# Shruthi-Analog-SMR4-mkII-v02-outline-log.net
KiCad netlist of a schematic drawn in EAGLE
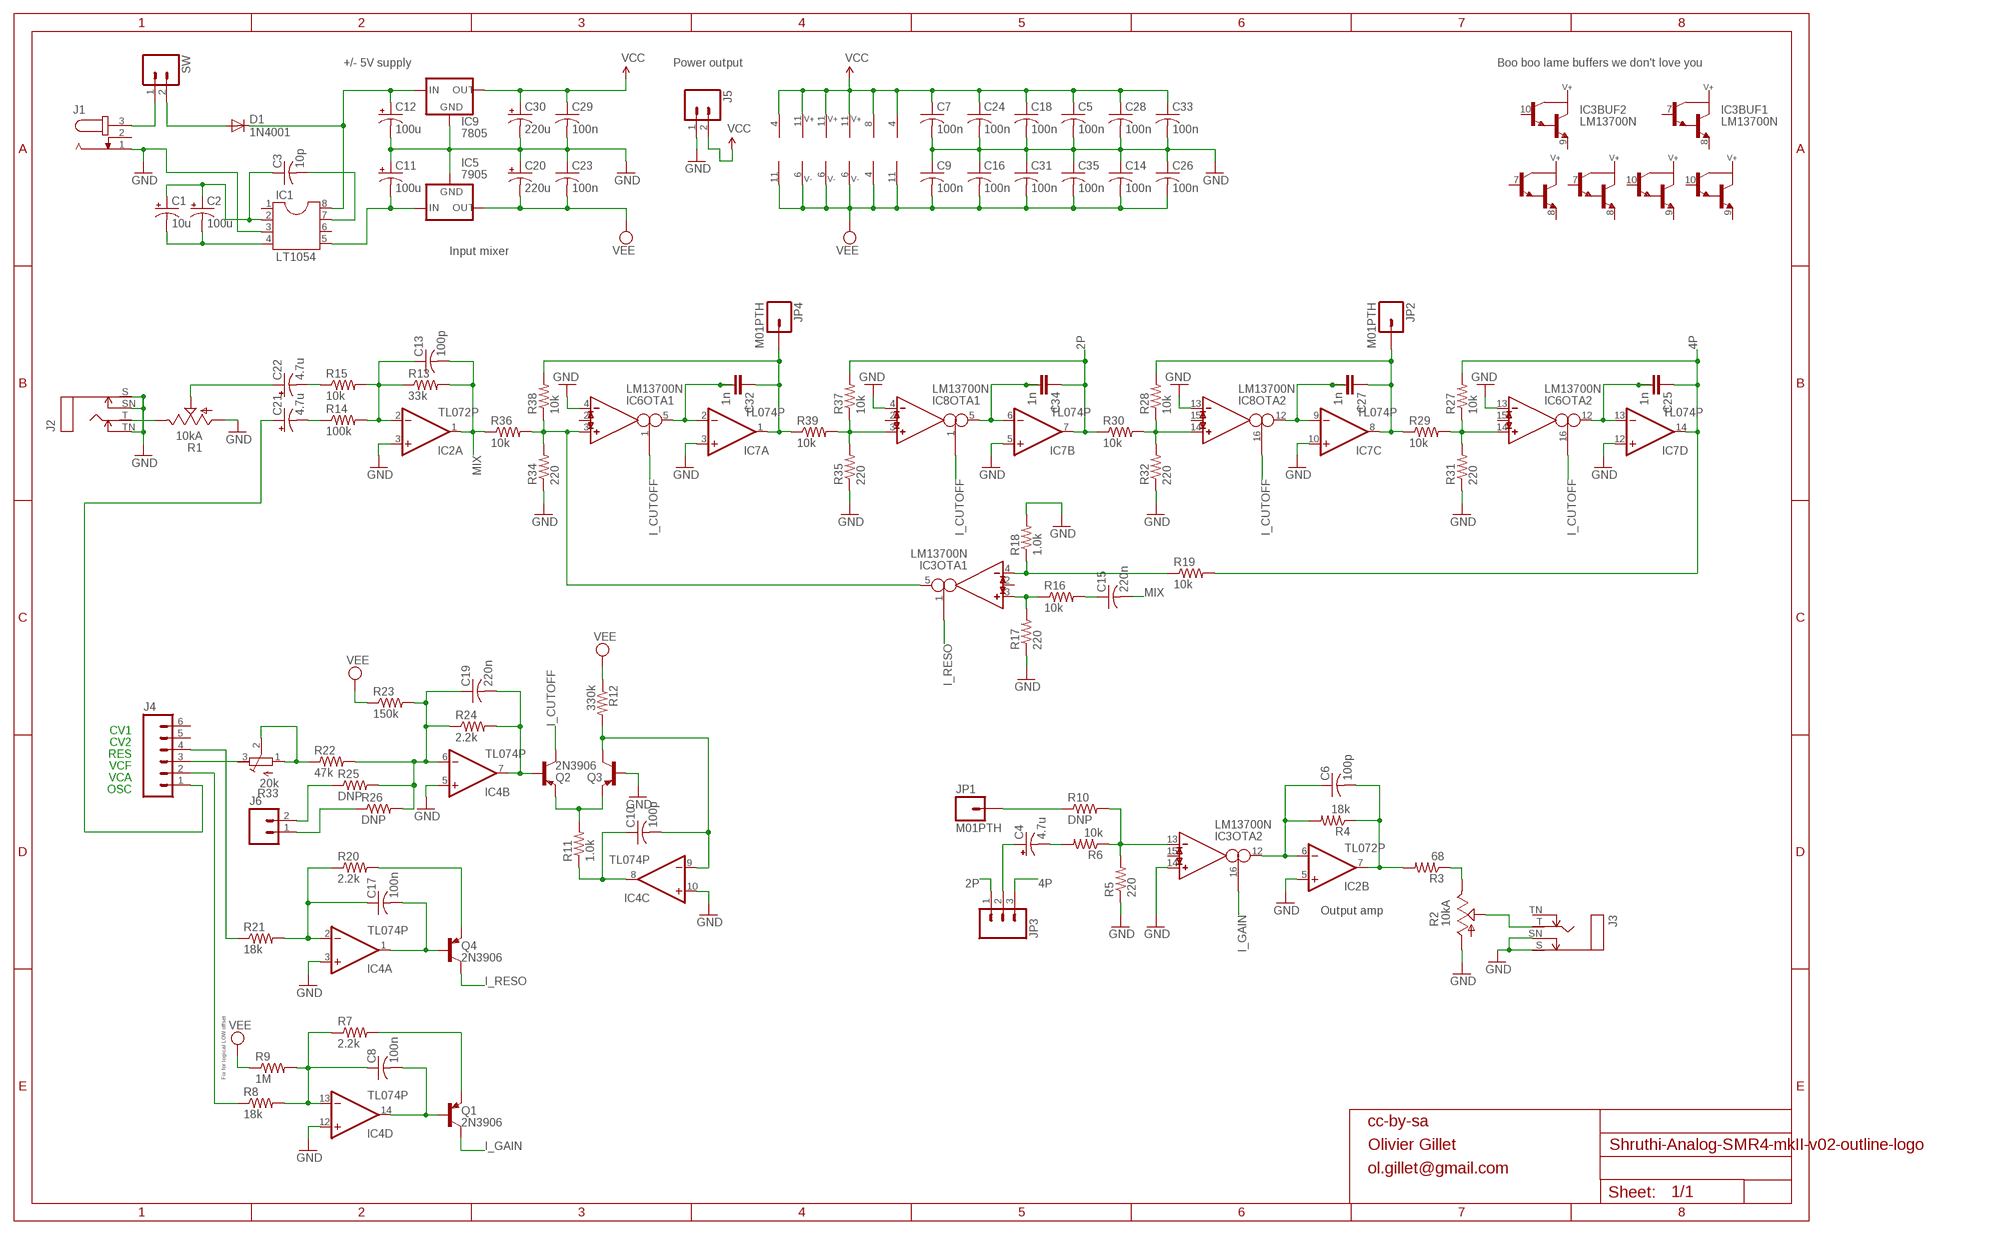
[diagram p0: schematic, sheet 1]

(export (version "E")
  (design (tool "Eeschema 10.0.6"))
  (components
    (comp (ref "C1")
      (value "10u")
      (footprint "eagle-import:E2,5-5")
      (libsource (lib "eagle-import") (part "CPOL-USE2.5-5"))
    )
    (comp (ref "C2")
      (value "100u")
      (footprint "eagle-import:E2,5-6")
      (libsource (lib "eagle-import") (part "CPOL-USE2.5-6"))
    )
    (comp (ref "C3")
      (value "10p")
      (footprint "eagle-import:C025-025X050")
      (libsource (lib "eagle-import") (part "C-US025-025X050"))
    )
    (comp (ref "C4")
      (value "4.7u")
      (footprint "eagle-import:E2,5-6")
      (libsource (lib "eagle-import") (part "CPOL-USE2.5-6"))
    )
    (comp (ref "C5")
      (value "100n")
      (footprint "eagle-import:C025-025X050")
      (libsource (lib "eagle-import") (part "C-US025-025X050"))
    )
    (comp (ref "C6")
      (value "100p")
      (footprint "eagle-import:C025-025X050")
      (libsource (lib "eagle-import") (part "C-US025-025X050"))
    )
    (comp (ref "C7")
      (value "100n")
      (footprint "eagle-import:C025-025X050")
      (libsource (lib "eagle-import") (part "C-US025-025X050"))
    )
    (comp (ref "C8")
      (value "100n")
      (footprint "eagle-import:C025-025X050")
      (libsource (lib "eagle-import") (part "C-US025-025X050"))
    )
    (comp (ref "C9")
      (value "100n")
      (footprint "eagle-import:C025-025X050")
      (libsource (lib "eagle-import") (part "C-US025-025X050"))
    )
    (comp (ref "C10")
      (value "100p")
      (footprint "eagle-import:C025-025X050")
      (libsource (lib "eagle-import") (part "C-US025-025X050"))
    )
    (comp (ref "C11")
      (value "100u")
      (footprint "eagle-import:E2,5-7")
      (libsource (lib "eagle-import") (part "CPOL-USE2.5-7"))
    )
    (comp (ref "C12")
      (value "100u")
      (footprint "eagle-import:E2,5-7")
      (libsource (lib "eagle-import") (part "CPOL-USE2.5-7"))
    )
    (comp (ref "C13")
      (value "100p")
      (footprint "eagle-import:C025-025X050")
      (libsource (lib "eagle-import") (part "C-US025-025X050"))
    )
    (comp (ref "C14")
      (value "100n")
      (footprint "eagle-import:C025-025X050")
      (libsource (lib "eagle-import") (part "C-US025-025X050"))
    )
    (comp (ref "C15")
      (value "220n")
      (footprint "eagle-import:C025-025X050")
      (libsource (lib "eagle-import") (part "C-US025-025X050"))
    )
    (comp (ref "C16")
      (value "100n")
      (footprint "eagle-import:C025-025X050")
      (libsource (lib "eagle-import") (part "C-US025-025X050"))
    )
    (comp (ref "C17")
      (value "100n")
      (footprint "eagle-import:C025-025X050")
      (libsource (lib "eagle-import") (part "C-US025-025X050"))
    )
    (comp (ref "C18")
      (value "100n")
      (footprint "eagle-import:C025-025X050")
      (libsource (lib "eagle-import") (part "C-US025-025X050"))
    )
    (comp (ref "C19")
      (value "220n")
      (footprint "eagle-import:C025-025X050")
      (libsource (lib "eagle-import") (part "C-US025-025X050"))
    )
    (comp (ref "C20")
      (value "220u")
      (footprint "eagle-import:E5-10,5")
      (libsource (lib "eagle-import") (part "CPOL-USE5-10.5"))
    )
    (comp (ref "C21")
      (value "4.7u")
      (footprint "eagle-import:E2,5-6")
      (libsource (lib "eagle-import") (part "CPOL-USE2.5-6"))
    )
    (comp (ref "C22")
      (value "4.7u")
      (footprint "eagle-import:E2,5-6")
      (libsource (lib "eagle-import") (part "CPOL-USE2.5-6"))
    )
    (comp (ref "C23")
      (value "100n")
      (footprint "eagle-import:C025-025X050")
      (libsource (lib "eagle-import") (part "C-US025-025X050"))
    )
    (comp (ref "C24")
      (value "100n")
      (footprint "eagle-import:C025-025X050")
      (libsource (lib "eagle-import") (part "C-US025-025X050"))
    )
    (comp (ref "C25")
      (value "1n")
      (footprint "eagle-import:C2.5_5-2")
      (libsource (lib "eagle-import") (part "C-2.5-5/2"))
    )
    (comp (ref "C26")
      (value "100n")
      (footprint "eagle-import:C025-025X050")
      (libsource (lib "eagle-import") (part "C-US025-025X050"))
    )
    (comp (ref "C27")
      (value "1n")
      (footprint "eagle-import:C2.5_5-2")
      (libsource (lib "eagle-import") (part "C-2.5-5/2"))
    )
    (comp (ref "C28")
      (value "100n")
      (footprint "eagle-import:C025-025X050")
      (libsource (lib "eagle-import") (part "C-US025-025X050"))
    )
    (comp (ref "C29")
      (value "100n")
      (footprint "eagle-import:C025-025X050")
      (libsource (lib "eagle-import") (part "C-US025-025X050"))
    )
    (comp (ref "C30")
      (value "220u")
      (footprint "eagle-import:E5-10,5")
      (libsource (lib "eagle-import") (part "CPOL-USE5-10.5"))
    )
    (comp (ref "C31")
      (value "100n")
      (footprint "eagle-import:C025-025X050")
      (libsource (lib "eagle-import") (part "C-US025-025X050"))
    )
    (comp (ref "C32")
      (value "1n")
      (footprint "eagle-import:C2.5_5-2")
      (libsource (lib "eagle-import") (part "C-2.5-5/2"))
    )
    (comp (ref "C33")
      (value "100n")
      (footprint "eagle-import:C025-025X050")
      (libsource (lib "eagle-import") (part "C-US025-025X050"))
    )
    (comp (ref "C34")
      (value "1n")
      (footprint "eagle-import:C2.5_5-2")
      (libsource (lib "eagle-import") (part "C-2.5-5/2"))
    )
    (comp (ref "C35")
      (value "100n")
      (footprint "eagle-import:C025-025X050")
      (libsource (lib "eagle-import") (part "C-US025-025X050"))
    )
    (comp (ref "D1")
      (value "1N4001")
      (footprint "eagle-import:DO41-10")
      (libsource (lib "eagle-import") (part "1N4004"))
    )
    (comp (ref "IC1")
      (value "LT1054")
      (footprint "eagle-import:DIL08")
      (libsource (lib "eagle-import") (part "DIL8"))
    )
    (comp (ref "IC2")
      (value "TL072P")
      (footprint "eagle-import:DIL08")
      (libsource (lib "eagle-import") (part "TL072P"))
    )
    (comp (ref "IC3")
      (value "LM13700N")
      (footprint "eagle-import:DIL16")
      (libsource (lib "eagle-import") (part "LM13700N"))
    )
    (comp (ref "IC4")
      (value "TL074P")
      (footprint "eagle-import:DIL14")
      (libsource (lib "eagle-import") (part "TL084P"))
    )
    (comp (ref "IC5")
      (value "7905")
      (footprint "eagle-import:79XXS")
      (libsource (lib "eagle-import") (part "79XXS"))
    )
    (comp (ref "IC6")
      (value "LM13700N")
      (footprint "eagle-import:DIL16")
      (libsource (lib "eagle-import") (part "LM13700N"))
    )
    (comp (ref "IC7")
      (value "TL074P")
      (footprint "eagle-import:DIL14")
      (libsource (lib "eagle-import") (part "TL084P"))
    )
    (comp (ref "IC8")
      (value "LM13700N")
      (footprint "eagle-import:DIL16")
      (libsource (lib "eagle-import") (part "LM13700N"))
    )
    (comp (ref "IC9")
      (value "7805")
      (footprint "eagle-import:78XXS")
      (libsource (lib "eagle-import") (part "78XXS"))
    )
    (comp (ref "J1")
      (value "JACK-PLUG2")
      (footprint "eagle-import:SPC4078_BIG_HOLES")
      (libsource (lib "eagle-import") (part "JACK-PLUG2"))
    )
    (comp (ref "J2")
      (value "MONOSWS")
      (footprint "eagle-import:NMJ4HC-S")
      (libsource (lib "eagle-import") (part "MONOSWS"))
    )
    (comp (ref "J3")
      (value "MONOSWS")
      (footprint "eagle-import:NMJ4HC-S")
      (libsource (lib "eagle-import") (part "MONOSWS"))
    )
    (comp (ref "J4")
      (value "M06SIP")
      (footprint "eagle-import:1X06")
      (libsource (lib "eagle-import") (part "M06SIP"))
    )
    (comp (ref "J5")
      (value "M02PTH")
      (footprint "eagle-import:1X02")
      (libsource (lib "eagle-import") (part "M02PTH"))
    )
    (comp (ref "J6")
      (value "M02PTH")
      (footprint "eagle-import:1X02")
      (libsource (lib "eagle-import") (part "M02PTH"))
    )
    (comp (ref "JP1")
      (value "M01PTH")
      (footprint "eagle-import:1X01")
      (libsource (lib "eagle-import") (part "M01PTH"))
    )
    (comp (ref "JP2")
      (value "M01PTH")
      (footprint "eagle-import:1X01")
      (libsource (lib "eagle-import") (part "M01PTH"))
    )
    (comp (ref "JP3")
      (value "M03PTH")
      (footprint "eagle-import:1X03")
      (libsource (lib "eagle-import") (part "M03PTH"))
    )
    (comp (ref "JP4")
      (value "M01PTH")
      (footprint "eagle-import:1X01")
      (libsource (lib "eagle-import") (part "M01PTH"))
    )
    (comp (ref "Q1")
      (value "2N3906")
      (footprint "eagle-import:TO92-")
      (libsource (lib "eagle-import") (part "2N3906-"))
    )
    (comp (ref "Q2")
      (value "2N3906")
      (footprint "eagle-import:TO92-")
      (libsource (lib "eagle-import") (part "2N3906-"))
    )
    (comp (ref "Q3")
      (value "2N3906")
      (footprint "eagle-import:TO92-")
      (libsource (lib "eagle-import") (part "2N3906-"))
    )
    (comp (ref "Q4")
      (value "2N3906")
      (footprint "eagle-import:TO92-")
      (libsource (lib "eagle-import") (part "2N3906-"))
    )
    (comp (ref "R1")
      (value "10kA")
      (footprint "eagle-import:CABLE_POT_6MM")
      (libsource (lib "eagle-import") (part "POT_USCABLED"))
    )
    (comp (ref "R2")
      (value "10kA")
      (footprint "eagle-import:CABLE_POT_6MM")
      (libsource (lib "eagle-import") (part "POT_USCABLED"))
    )
    (comp (ref "R3")
      (value "68")
      (footprint "eagle-import:0204_7")
      (libsource (lib "eagle-import") (part "R-US_0204/7"))
    )
    (comp (ref "R4")
      (value "18k")
      (footprint "eagle-import:0204_7")
      (libsource (lib "eagle-import") (part "R-US_0204/7"))
    )
    (comp (ref "R5")
      (value "220")
      (footprint "eagle-import:0204_7")
      (libsource (lib "eagle-import") (part "R-US_0204/7"))
    )
    (comp (ref "R6")
      (value "10k")
      (footprint "eagle-import:0204_7")
      (libsource (lib "eagle-import") (part "R-US_0204/7"))
    )
    (comp (ref "R7")
      (value "2.2k")
      (footprint "eagle-import:0204_7")
      (libsource (lib "eagle-import") (part "R-US_0204/7"))
    )
    (comp (ref "R8")
      (value "18k")
      (footprint "eagle-import:0204_7")
      (libsource (lib "eagle-import") (part "R-US_0204/7"))
    )
    (comp (ref "R9")
      (value "1M")
      (footprint "eagle-import:0204_7")
      (libsource (lib "eagle-import") (part "R-US_0204/7"))
    )
    (comp (ref "R10")
      (value "DNP")
      (footprint "eagle-import:0204V")
      (libsource (lib "eagle-import") (part "R-US_0204/2V"))
    )
    (comp (ref "R11")
      (value "1.0k")
      (footprint "eagle-import:0204_7")
      (libsource (lib "eagle-import") (part "R-US_0204/7"))
    )
    (comp (ref "R12")
      (value "330k")
      (footprint "eagle-import:0204_7")
      (libsource (lib "eagle-import") (part "R-US_0204/7"))
    )
    (comp (ref "R13")
      (value "33k")
      (footprint "eagle-import:0204_7")
      (libsource (lib "eagle-import") (part "R-US_0204/7"))
    )
    (comp (ref "R14")
      (value "100k")
      (footprint "eagle-import:0204_7")
      (libsource (lib "eagle-import") (part "R-US_0204/7"))
    )
    (comp (ref "R15")
      (value "10k")
      (footprint "eagle-import:0204_7")
      (libsource (lib "eagle-import") (part "R-US_0204/7"))
    )
    (comp (ref "R16")
      (value "10k")
      (footprint "eagle-import:0204_7")
      (libsource (lib "eagle-import") (part "R-US_0204/7"))
    )
    (comp (ref "R17")
      (value "220")
      (footprint "eagle-import:0204_7")
      (libsource (lib "eagle-import") (part "R-US_0204/7"))
    )
    (comp (ref "R18")
      (value "1.0k")
      (footprint "eagle-import:0204_7")
      (libsource (lib "eagle-import") (part "R-US_0204/7"))
    )
    (comp (ref "R19")
      (value "10k")
      (footprint "eagle-import:0204_7")
      (libsource (lib "eagle-import") (part "R-US_0204/7"))
    )
    (comp (ref "R20")
      (value "2.2k")
      (footprint "eagle-import:0204_7")
      (libsource (lib "eagle-import") (part "R-US_0204/7"))
    )
    (comp (ref "R21")
      (value "18k")
      (footprint "eagle-import:0204_7")
      (libsource (lib "eagle-import") (part "R-US_0204/7"))
    )
    (comp (ref "R22")
      (value "47k")
      (footprint "eagle-import:0204_7")
      (libsource (lib "eagle-import") (part "R-US_0204/7"))
    )
    (comp (ref "R23")
      (value "150k")
      (footprint "eagle-import:0204_7")
      (libsource (lib "eagle-import") (part "R-US_0204/7"))
    )
    (comp (ref "R24")
      (value "2.2k")
      (footprint "eagle-import:0204_7")
      (libsource (lib "eagle-import") (part "R-US_0204/7"))
    )
    (comp (ref "R25")
      (value "DNP")
      (footprint "eagle-import:0204V")
      (libsource (lib "eagle-import") (part "R-US_0204/2V"))
    )
    (comp (ref "R26")
      (value "DNP")
      (footprint "eagle-import:0204V")
      (libsource (lib "eagle-import") (part "R-US_0204/2V"))
    )
    (comp (ref "R27")
      (value "10k")
      (footprint "eagle-import:0204_7")
      (libsource (lib "eagle-import") (part "R-US_0204/7"))
    )
    (comp (ref "R28")
      (value "10k")
      (footprint "eagle-import:0204_7")
      (libsource (lib "eagle-import") (part "R-US_0204/7"))
    )
    (comp (ref "R29")
      (value "10k")
      (footprint "eagle-import:0204_7")
      (libsource (lib "eagle-import") (part "R-US_0204/7"))
    )
    (comp (ref "R30")
      (value "10k")
      (footprint "eagle-import:0204_7")
      (libsource (lib "eagle-import") (part "R-US_0204/7"))
    )
    (comp (ref "R31")
      (value "220")
      (footprint "eagle-import:0204_7")
      (libsource (lib "eagle-import") (part "R-US_0204/7"))
    )
    (comp (ref "R32")
      (value "220")
      (footprint "eagle-import:0204_7")
      (libsource (lib "eagle-import") (part "R-US_0204/7"))
    )
    (comp (ref "R33")
      (value "20k")
      (footprint "eagle-import:RTRIM3296X")
      (libsource (lib "eagle-import") (part "R-TRIMM3296X"))
    )
    (comp (ref "R34")
      (value "220")
      (footprint "eagle-import:0204_7")
      (libsource (lib "eagle-import") (part "R-US_0204/7"))
    )
    (comp (ref "R35")
      (value "220")
      (footprint "eagle-import:0204_7")
      (libsource (lib "eagle-import") (part "R-US_0204/7"))
    )
    (comp (ref "R36")
      (value "10k")
      (footprint "eagle-import:0204_7")
      (libsource (lib "eagle-import") (part "R-US_0204/7"))
    )
    (comp (ref "R37")
      (value "10k")
      (footprint "eagle-import:0204_7")
      (libsource (lib "eagle-import") (part "R-US_0204/7"))
    )
    (comp (ref "R38")
      (value "10k")
      (footprint "eagle-import:0204_7")
      (libsource (lib "eagle-import") (part "R-US_0204/7"))
    )
    (comp (ref "R39")
      (value "10k")
      (footprint "eagle-import:0204_7")
      (libsource (lib "eagle-import") (part "R-US_0204/7"))
    )
    (comp (ref "SW")
      (value "M02PTH")
      (footprint "eagle-import:1X02")
      (libsource (lib "eagle-import") (part "M02PTH"))
    )
  )
  (nets
    (net (code "1") (name "/2P") (class "Default")
      (node (ref "C34") (pin "1") (pinfunction "1_1") (pintype "passive"))
      (node (ref "IC7") (pin "7") (pinfunction "OUT_7") (pintype "output"))
      (node (ref "JP3") (pin "1") (pinfunction "1_1") (pintype "passive"))
      (node (ref "R30") (pin "1") (pinfunction "1_1") (pintype "passive"))
      (node (ref "R37") (pin "2") (pinfunction "2_2") (pintype "passive"))
    )
    (net (code "2") (name "/4P") (class "Default")
      (node (ref "C25") (pin "1") (pinfunction "1_1") (pintype "passive"))
      (node (ref "IC7") (pin "14") (pinfunction "OUT_14") (pintype "output"))
      (node (ref "JP3") (pin "3") (pinfunction "3_3") (pintype "passive"))
      (node (ref "R19") (pin "2") (pinfunction "2_2") (pintype "passive"))
      (node (ref "R27") (pin "2") (pinfunction "2_2") (pintype "passive"))
    )
    (net (code "3") (name "/I_CUTOFF") (class "Default")
      (node (ref "IC6") (pin "1") (pinfunction "I_BIAS_1") (pintype "input"))
      (node (ref "IC6") (pin "16") (pinfunction "I_BIAS_16") (pintype "input"))
      (node (ref "IC8") (pin "1") (pinfunction "I_BIAS_1") (pintype "input"))
      (node (ref "IC8") (pin "16") (pinfunction "I_BIAS_16") (pintype "input"))
      (node (ref "Q2") (pin "1") (pinfunction "C_1") (pintype "passive"))
    )
    (net (code "4") (name "/I_GAIN") (class "Default")
      (node (ref "IC3") (pin "16") (pinfunction "I_BIAS_16") (pintype "input"))
      (node (ref "Q1") (pin "1") (pinfunction "C_1") (pintype "passive"))
    )
    (net (code "5") (name "/I_RESO") (class "Default")
      (node (ref "IC3") (pin "1") (pinfunction "I_BIAS_1") (pintype "input"))
      (node (ref "Q4") (pin "1") (pinfunction "C_1") (pintype "passive"))
    )
    (net (code "6") (name "/MIX") (class "Default")
      (node (ref "C13") (pin "2") (pinfunction "2_2") (pintype "passive"))
      (node (ref "C15") (pin "2") (pinfunction "2_2") (pintype "passive"))
      (node (ref "IC2") (pin "1") (pinfunction "OUT_1") (pintype "output"))
      (node (ref "R13") (pin "2") (pinfunction "2_2") (pintype "passive"))
      (node (ref "R36") (pin "1") (pinfunction "1_1") (pintype "passive"))
    )
    (net (code "7") (name "GND") (class "Default")
      (node (ref "C11") (pin "+") (pinfunction "+_+") (pintype "passive"))
      (node (ref "C12") (pin "-") (pinfunction "-_-") (pintype "passive"))
      (node (ref "C14") (pin "1") (pinfunction "1_1") (pintype "passive"))
      (node (ref "C16") (pin "1") (pinfunction "1_1") (pintype "passive"))
      (node (ref "C18") (pin "2") (pinfunction "2_2") (pintype "passive"))
      (node (ref "C20") (pin "+") (pinfunction "+_+") (pintype "passive"))
      (node (ref "C23") (pin "1") (pinfunction "1_1") (pintype "passive"))
      (node (ref "C24") (pin "2") (pinfunction "2_2") (pintype "passive"))
      (node (ref "C26") (pin "1") (pinfunction "1_1") (pintype "passive"))
      (node (ref "C28") (pin "2") (pinfunction "2_2") (pintype "passive"))
      (node (ref "C29") (pin "2") (pinfunction "2_2") (pintype "passive"))
      (node (ref "C30") (pin "-") (pinfunction "-_-") (pintype "passive"))
      (node (ref "C31") (pin "1") (pinfunction "1_1") (pintype "passive"))
      (node (ref "C33") (pin "2") (pinfunction "2_2") (pintype "passive"))
      (node (ref "C35") (pin "1") (pinfunction "1_1") (pintype "passive"))
      (node (ref "C5") (pin "2") (pinfunction "2_2") (pintype "passive"))
      (node (ref "C7") (pin "2") (pinfunction "2_2") (pintype "passive"))
      (node (ref "C9") (pin "1") (pinfunction "1_1") (pintype "passive"))
      (node (ref "IC1") (pin "3") (pinfunction "3_3") (pintype "passive"))
      (node (ref "IC2") (pin "3") (pinfunction "+IN_3") (pintype "input"))
      (node (ref "IC2") (pin "5") (pinfunction "+IN_5") (pintype "input"))
      (node (ref "IC3") (pin "14") (pinfunction "IN_P_14") (pintype "input"))
      (node (ref "IC4") (pin "10") (pinfunction "+IN_10") (pintype "input"))
      (node (ref "IC4") (pin "12") (pinfunction "+IN_12") (pintype "input"))
      (node (ref "IC4") (pin "3") (pinfunction "+IN_3") (pintype "input"))
      (node (ref "IC4") (pin "5") (pinfunction "+IN_5") (pintype "input"))
      (node (ref "IC5") (pin "GND") (pinfunction "GND_GND") (pintype "input"))
      (node (ref "IC6") (pin "13") (pinfunction "IN_N_13") (pintype "input"))
      (node (ref "IC6") (pin "4") (pinfunction "IN_N_4") (pintype "input"))
      (node (ref "IC7") (pin "10") (pinfunction "+IN_10") (pintype "input"))
      (node (ref "IC7") (pin "12") (pinfunction "+IN_12") (pintype "input"))
      (node (ref "IC7") (pin "3") (pinfunction "+IN_3") (pintype "input"))
      (node (ref "IC7") (pin "5") (pinfunction "+IN_5") (pintype "input"))
      (node (ref "IC8") (pin "13") (pinfunction "IN_N_13") (pintype "input"))
      (node (ref "IC8") (pin "4") (pinfunction "IN_N_4") (pintype "input"))
      (node (ref "IC9") (pin "GND") (pinfunction "GND_GND") (pintype "input"))
      (node (ref "J1") (pin "1") (pinfunction "1_1") (pintype "passive"))
      (node (ref "J2") (pin "S") (pinfunction "S_S") (pintype "passive"))
      (node (ref "J2") (pin "SN") (pinfunction "SN_SN") (pintype "passive"))
      (node (ref "J2") (pin "TN") (pinfunction "TN_TN") (pintype "passive"))
      (node (ref "J3") (pin "S") (pinfunction "S_S") (pintype "passive"))
      (node (ref "J3") (pin "SN") (pinfunction "SN_SN") (pintype "passive"))
      (node (ref "J5") (pin "1") (pinfunction "1_1") (pintype "passive"))
      (node (ref "Q3") (pin "2") (pinfunction "B_2") (pintype "passive"))
      (node (ref "R1") (pin "A") (pinfunction "A_A") (pintype "passive"))
      (node (ref "R17") (pin "1") (pinfunction "1_1") (pintype "passive"))
      (node (ref "R18") (pin "2") (pinfunction "2_2") (pintype "passive"))
      (node (ref "R2") (pin "A") (pinfunction "A_A") (pintype "passive"))
      (node (ref "R31") (pin "1") (pinfunction "1_1") (pintype "passive"))
      (node (ref "R32") (pin "1") (pinfunction "1_1") (pintype "passive"))
      (node (ref "R34") (pin "1") (pinfunction "1_1") (pintype "passive"))
      (node (ref "R35") (pin "1") (pinfunction "1_1") (pintype "passive"))
      (node (ref "R5") (pin "1") (pinfunction "1_1") (pintype "passive"))
    )
    (net (code "8") (name "Net-(C1-Pad+)") (class "Default")
      (node (ref "C1") (pin "+") (pinfunction "+_+") (pintype "passive"))
      (node (ref "C2") (pin "+") (pinfunction "+_+") (pintype "passive"))
      (node (ref "C3") (pin "1") (pinfunction "1_1") (pintype "passive"))
      (node (ref "IC1") (pin "2") (pinfunction "2_2") (pintype "passive"))
    )
    (net (code "9") (name "Net-(C1-Pad-)") (class "Default")
      (node (ref "C1") (pin "-") (pinfunction "-_-") (pintype "passive"))
      (node (ref "C2") (pin "-") (pinfunction "-_-") (pintype "passive"))
      (node (ref "IC1") (pin "4") (pinfunction "4_4") (pintype "passive"))
    )
    (net (code "10") (name "Net-(C3-Pad2)") (class "Default")
      (node (ref "C3") (pin "2") (pinfunction "2_2") (pintype "passive"))
      (node (ref "IC1") (pin "7") (pinfunction "7_7") (pintype "passive"))
    )
    (net (code "11") (name "Net-(C4-Pad+)") (class "Default")
      (node (ref "C4") (pin "+") (pinfunction "+_+") (pintype "passive"))
      (node (ref "JP3") (pin "2") (pinfunction "2_2") (pintype "passive"))
    )
    (net (code "12") (name "Net-(C4-Pad-)") (class "Default")
      (node (ref "C4") (pin "-") (pinfunction "-_-") (pintype "passive"))
      (node (ref "R6") (pin "2") (pinfunction "2_2") (pintype "passive"))
    )
    (net (code "13") (name "Net-(C11-Pad-)") (class "Default")
      (node (ref "C11") (pin "-") (pinfunction "-_-") (pintype "passive"))
      (node (ref "IC1") (pin "5") (pinfunction "5_5") (pintype "passive"))
      (node (ref "IC5") (pin "IN") (pinfunction "IN_IN") (pintype "input"))
    )
    (net (code "14") (name "Net-(C12-Pad+)") (class "Default")
      (node (ref "C12") (pin "+") (pinfunction "+_+") (pintype "passive"))
      (node (ref "D1") (pin "C") (pinfunction "C_C") (pintype "passive"))
      (node (ref "IC1") (pin "8") (pinfunction "8_8") (pintype "passive"))
      (node (ref "IC9") (pin "IN") (pinfunction "IN_IN") (pintype "input"))
    )
    (net (code "15") (name "Net-(C15-Pad1)") (class "Default")
      (node (ref "C15") (pin "1") (pinfunction "1_1") (pintype "passive"))
      (node (ref "R16") (pin "2") (pinfunction "2_2") (pintype "passive"))
    )
    (net (code "16") (name "Net-(C21-Pad+)") (class "Default")
      (node (ref "C21") (pin "+") (pinfunction "+_+") (pintype "passive"))
      (node (ref "J4") (pin "1") (pinfunction "1_1") (pintype "passive"))
    )
    (net (code "17") (name "Net-(C21-Pad-)") (class "Default")
      (node (ref "C21") (pin "-") (pinfunction "-_-") (pintype "passive"))
      (node (ref "R14") (pin "1") (pinfunction "1_1") (pintype "passive"))
    )
    (net (code "18") (name "Net-(C22-Pad+)") (class "Default")
      (node (ref "C22") (pin "+") (pinfunction "+_+") (pintype "passive"))
      (node (ref "R1") (pin "S") (pinfunction "S_S") (pintype "passive"))
    )
    (net (code "19") (name "Net-(C22-Pad-)") (class "Default")
      (node (ref "C22") (pin "-") (pinfunction "-_-") (pintype "passive"))
      (node (ref "R15") (pin "1") (pinfunction "1_1") (pintype "passive"))
    )
    (net (code "20") (name "Net-(D1-PadA)") (class "Default")
      (node (ref "D1") (pin "A") (pinfunction "A_A") (pintype "passive"))
      (node (ref "SW") (pin "2") (pinfunction "2_2") (pintype "passive"))
    )
    (net (code "21") (name "Net-(IC2A--IN)") (class "Default")
      (node (ref "C13") (pin "1") (pinfunction "1_1") (pintype "passive"))
      (node (ref "IC2") (pin "2") (pinfunction "-IN_2") (pintype "input"))
      (node (ref "R13") (pin "1") (pinfunction "1_1") (pintype "passive"))
      (node (ref "R14") (pin "2") (pinfunction "2_2") (pintype "passive"))
      (node (ref "R15") (pin "2") (pinfunction "2_2") (pintype "passive"))
    )
    (net (code "22") (name "Net-(IC2B--IN)") (class "Default")
      (node (ref "C6") (pin "1") (pinfunction "1_1") (pintype "passive"))
      (node (ref "IC2") (pin "6") (pinfunction "-IN_6") (pintype "input"))
      (node (ref "IC3") (pin "12") (pinfunction "OUT_12") (pintype "output"))
      (node (ref "R4") (pin "2") (pinfunction "2_2") (pintype "passive"))
    )
    (net (code "23") (name "Net-(IC2B-OUT)") (class "Default")
      (node (ref "C6") (pin "2") (pinfunction "2_2") (pintype "passive"))
      (node (ref "IC2") (pin "7") (pinfunction "OUT_7") (pintype "output"))
      (node (ref "R3") (pin "2") (pinfunction "2_2") (pintype "passive"))
      (node (ref "R4") (pin "1") (pinfunction "1_1") (pintype "passive"))
    )
    (net (code "24") (name "Net-(IC3C-IN_N)") (class "Default")
      (node (ref "IC3") (pin "4") (pinfunction "IN_N_4") (pintype "input"))
      (node (ref "R18") (pin "1") (pinfunction "1_1") (pintype "passive"))
      (node (ref "R19") (pin "1") (pinfunction "1_1") (pintype "passive"))
    )
    (net (code "25") (name "Net-(IC3C-IN_P)") (class "Default")
      (node (ref "IC3") (pin "3") (pinfunction "IN_P_3") (pintype "input"))
      (node (ref "R16") (pin "1") (pinfunction "1_1") (pintype "passive"))
      (node (ref "R17") (pin "2") (pinfunction "2_2") (pintype "passive"))
    )
    (net (code "26") (name "Net-(IC3C-OUT)") (class "Default")
      (node (ref "IC3") (pin "5") (pinfunction "OUT_5") (pintype "output"))
      (node (ref "IC6") (pin "3") (pinfunction "IN_P_3") (pintype "input"))
      (node (ref "R34") (pin "2") (pinfunction "2_2") (pintype "passive"))
      (node (ref "R36") (pin "2") (pinfunction "2_2") (pintype "passive"))
      (node (ref "R38") (pin "1") (pinfunction "1_1") (pintype "passive"))
    )
    (net (code "27") (name "Net-(IC3D-IN_N)") (class "Default")
      (node (ref "IC3") (pin "13") (pinfunction "IN_N_13") (pintype "input"))
      (node (ref "R10") (pin "2") (pinfunction "2_2") (pintype "passive"))
      (node (ref "R5") (pin "2") (pinfunction "2_2") (pintype "passive"))
      (node (ref "R6") (pin "1") (pinfunction "1_1") (pintype "passive"))
    )
    (net (code "28") (name "Net-(IC4A--IN)") (class "Default")
      (node (ref "C17") (pin "1") (pinfunction "1_1") (pintype "passive"))
      (node (ref "IC4") (pin "2") (pinfunction "-IN_2") (pintype "input"))
      (node (ref "R20") (pin "1") (pinfunction "1_1") (pintype "passive"))
      (node (ref "R21") (pin "2") (pinfunction "2_2") (pintype "passive"))
    )
    (net (code "29") (name "Net-(IC4A-OUT)") (class "Default")
      (node (ref "C17") (pin "2") (pinfunction "2_2") (pintype "passive"))
      (node (ref "IC4") (pin "1") (pinfunction "OUT_1") (pintype "output"))
      (node (ref "Q4") (pin "2") (pinfunction "B_2") (pintype "passive"))
    )
    (net (code "30") (name "Net-(IC4B--IN)") (class "Default")
      (node (ref "C19") (pin "1") (pinfunction "1_1") (pintype "passive"))
      (node (ref "IC4") (pin "6") (pinfunction "-IN_6") (pintype "input"))
      (node (ref "R22") (pin "2") (pinfunction "2_2") (pintype "passive"))
      (node (ref "R23") (pin "2") (pinfunction "2_2") (pintype "passive"))
      (node (ref "R24") (pin "1") (pinfunction "1_1") (pintype "passive"))
      (node (ref "R25") (pin "2") (pinfunction "2_2") (pintype "passive"))
      (node (ref "R26") (pin "2") (pinfunction "2_2") (pintype "passive"))
    )
    (net (code "31") (name "Net-(IC4B-OUT)") (class "Default")
      (node (ref "C19") (pin "2") (pinfunction "2_2") (pintype "passive"))
      (node (ref "IC4") (pin "7") (pinfunction "OUT_7") (pintype "output"))
      (node (ref "Q2") (pin "2") (pinfunction "B_2") (pintype "passive"))
      (node (ref "R24") (pin "2") (pinfunction "2_2") (pintype "passive"))
    )
    (net (code "32") (name "Net-(IC4C--IN)") (class "Default")
      (node (ref "C10") (pin "2") (pinfunction "2_2") (pintype "passive"))
      (node (ref "IC4") (pin "9") (pinfunction "-IN_9") (pintype "input"))
      (node (ref "Q3") (pin "1") (pinfunction "C_1") (pintype "passive"))
      (node (ref "R12") (pin "2") (pinfunction "2_2") (pintype "passive"))
    )
    (net (code "33") (name "Net-(IC4C-OUT)") (class "Default")
      (node (ref "C10") (pin "1") (pinfunction "1_1") (pintype "passive"))
      (node (ref "IC4") (pin "8") (pinfunction "OUT_8") (pintype "output"))
      (node (ref "R11") (pin "1") (pinfunction "1_1") (pintype "passive"))
    )
    (net (code "34") (name "Net-(IC4D--IN)") (class "Default")
      (node (ref "C8") (pin "1") (pinfunction "1_1") (pintype "passive"))
      (node (ref "IC4") (pin "13") (pinfunction "-IN_13") (pintype "input"))
      (node (ref "R7") (pin "1") (pinfunction "1_1") (pintype "passive"))
      (node (ref "R8") (pin "2") (pinfunction "2_2") (pintype "passive"))
      (node (ref "R9") (pin "2") (pinfunction "2_2") (pintype "passive"))
    )
    (net (code "35") (name "Net-(IC4D-OUT)") (class "Default")
      (node (ref "C8") (pin "2") (pinfunction "2_2") (pintype "passive"))
      (node (ref "IC4") (pin "14") (pinfunction "OUT_14") (pintype "output"))
      (node (ref "Q1") (pin "2") (pinfunction "B_2") (pintype "passive"))
    )
    (net (code "36") (name "Net-(IC6C-OUT)") (class "Default")
      (node (ref "C32") (pin "2") (pinfunction "2_2") (pintype "passive"))
      (node (ref "C32") (pin "3") (pinfunction "3_3") (pintype "passive"))
      (node (ref "IC6") (pin "5") (pinfunction "OUT_5") (pintype "output"))
      (node (ref "IC7") (pin "2") (pinfunction "-IN_2") (pintype "input"))
    )
    (net (code "37") (name "Net-(IC6D-IN_P)") (class "Default")
      (node (ref "IC6") (pin "14") (pinfunction "IN_P_14") (pintype "input"))
      (node (ref "R27") (pin "1") (pinfunction "1_1") (pintype "passive"))
      (node (ref "R29") (pin "2") (pinfunction "2_2") (pintype "passive"))
      (node (ref "R31") (pin "2") (pinfunction "2_2") (pintype "passive"))
    )
    (net (code "38") (name "Net-(IC6D-OUT)") (class "Default")
      (node (ref "C25") (pin "2") (pinfunction "2_2") (pintype "passive"))
      (node (ref "C25") (pin "3") (pinfunction "3_3") (pintype "passive"))
      (node (ref "IC6") (pin "12") (pinfunction "OUT_12") (pintype "output"))
      (node (ref "IC7") (pin "13") (pinfunction "-IN_13") (pintype "input"))
    )
    (net (code "39") (name "Net-(IC7A-OUT)") (class "Default")
      (node (ref "C32") (pin "1") (pinfunction "1_1") (pintype "passive"))
      (node (ref "IC7") (pin "1") (pinfunction "OUT_1") (pintype "output"))
      (node (ref "JP4") (pin "1") (pinfunction "1_1") (pintype "passive"))
      (node (ref "R38") (pin "2") (pinfunction "2_2") (pintype "passive"))
      (node (ref "R39") (pin "1") (pinfunction "1_1") (pintype "passive"))
    )
    (net (code "40") (name "Net-(IC7B--IN)") (class "Default")
      (node (ref "C34") (pin "2") (pinfunction "2_2") (pintype "passive"))
      (node (ref "C34") (pin "3") (pinfunction "3_3") (pintype "passive"))
      (node (ref "IC7") (pin "6") (pinfunction "-IN_6") (pintype "input"))
      (node (ref "IC8") (pin "5") (pinfunction "OUT_5") (pintype "output"))
    )
    (net (code "41") (name "Net-(IC7C--IN)") (class "Default")
      (node (ref "C27") (pin "2") (pinfunction "2_2") (pintype "passive"))
      (node (ref "C27") (pin "3") (pinfunction "3_3") (pintype "passive"))
      (node (ref "IC7") (pin "9") (pinfunction "-IN_9") (pintype "input"))
      (node (ref "IC8") (pin "12") (pinfunction "OUT_12") (pintype "output"))
    )
    (net (code "42") (name "Net-(IC7C-OUT)") (class "Default")
      (node (ref "C27") (pin "1") (pinfunction "1_1") (pintype "passive"))
      (node (ref "IC7") (pin "8") (pinfunction "OUT_8") (pintype "output"))
      (node (ref "JP2") (pin "1") (pinfunction "1_1") (pintype "passive"))
      (node (ref "R28") (pin "2") (pinfunction "2_2") (pintype "passive"))
      (node (ref "R29") (pin "1") (pinfunction "1_1") (pintype "passive"))
    )
    (net (code "43") (name "Net-(IC8C-IN_P)") (class "Default")
      (node (ref "IC8") (pin "3") (pinfunction "IN_P_3") (pintype "input"))
      (node (ref "R35") (pin "2") (pinfunction "2_2") (pintype "passive"))
      (node (ref "R37") (pin "1") (pinfunction "1_1") (pintype "passive"))
      (node (ref "R39") (pin "2") (pinfunction "2_2") (pintype "passive"))
    )
    (net (code "44") (name "Net-(IC8D-IN_P)") (class "Default")
      (node (ref "IC8") (pin "14") (pinfunction "IN_P_14") (pintype "input"))
      (node (ref "R28") (pin "1") (pinfunction "1_1") (pintype "passive"))
      (node (ref "R30") (pin "2") (pinfunction "2_2") (pintype "passive"))
      (node (ref "R32") (pin "2") (pinfunction "2_2") (pintype "passive"))
    )
    (net (code "45") (name "Net-(J1-Pad3)") (class "Default")
      (node (ref "J1") (pin "3") (pinfunction "3_3") (pintype "passive"))
      (node (ref "SW") (pin "1") (pinfunction "1_1") (pintype "passive"))
    )
    (net (code "46") (name "Net-(J2-PadT)") (class "Default")
      (node (ref "J2") (pin "T") (pinfunction "T_T") (pintype "passive"))
      (node (ref "R1") (pin "E") (pinfunction "E_E") (pintype "passive"))
    )
    (net (code "47") (name "Net-(J3-PadT)") (class "Default")
      (node (ref "J3") (pin "T") (pinfunction "T_T") (pintype "passive"))
      (node (ref "R2") (pin "S") (pinfunction "S_S") (pintype "passive"))
    )
    (net (code "48") (name "Net-(J4-Pad2)") (class "Default")
      (node (ref "J4") (pin "2") (pinfunction "2_2") (pintype "passive"))
      (node (ref "R8") (pin "1") (pinfunction "1_1") (pintype "passive"))
    )
    (net (code "49") (name "Net-(J4-Pad4)") (class "Default")
      (node (ref "J4") (pin "4") (pinfunction "4_4") (pintype "passive"))
      (node (ref "R21") (pin "1") (pinfunction "1_1") (pintype "passive"))
    )
    (net (code "50") (name "Net-(J6-Pad1)") (class "Default")
      (node (ref "J6") (pin "1") (pinfunction "1_1") (pintype "passive"))
      (node (ref "R26") (pin "1") (pinfunction "1_1") (pintype "passive"))
    )
    (net (code "51") (name "Net-(J6-Pad2)") (class "Default")
      (node (ref "J6") (pin "2") (pinfunction "2_2") (pintype "passive"))
      (node (ref "R25") (pin "1") (pinfunction "1_1") (pintype "passive"))
    )
    (net (code "52") (name "Net-(JP1-Pad1)") (class "Default")
      (node (ref "JP1") (pin "1") (pinfunction "1_1") (pintype "passive"))
      (node (ref "R10") (pin "1") (pinfunction "1_1") (pintype "passive"))
    )
    (net (code "53") (name "Net-(Q1-E)") (class "Default")
      (node (ref "Q1") (pin "3") (pinfunction "E_3") (pintype "passive"))
      (node (ref "R7") (pin "2") (pinfunction "2_2") (pintype "passive"))
    )
    (net (code "54") (name "Net-(Q2-E)") (class "Default")
      (node (ref "Q2") (pin "3") (pinfunction "E_3") (pintype "passive"))
      (node (ref "Q3") (pin "3") (pinfunction "E_3") (pintype "passive"))
      (node (ref "R11") (pin "2") (pinfunction "2_2") (pintype "passive"))
    )
    (net (code "55") (name "Net-(Q4-E)") (class "Default")
      (node (ref "Q4") (pin "3") (pinfunction "E_3") (pintype "passive"))
      (node (ref "R20") (pin "2") (pinfunction "2_2") (pintype "passive"))
    )
    (net (code "56") (name "Net-(R2-PadE)") (class "Default")
      (node (ref "R2") (pin "E") (pinfunction "E_E") (pintype "passive"))
      (node (ref "R3") (pin "1") (pinfunction "1_1") (pintype "passive"))
    )
    (net (code "57") (name "Net-(R33-A)") (class "Default")
      (node (ref "J4") (pin "3") (pinfunction "3_3") (pintype "passive"))
      (node (ref "R33") (pin "3") (pinfunction "A_3") (pintype "passive"))
    )
    (net (code "58") (name "Net-(R33-E)") (class "Default")
      (node (ref "R22") (pin "1") (pinfunction "1_1") (pintype "passive"))
      (node (ref "R33") (pin "1") (pinfunction "E_1") (pintype "passive"))
      (node (ref "R33") (pin "2") (pinfunction "S_2") (pintype "passive"))
    )
    (net (code "59") (name "VCC") (class "Default")
      (node (ref "C18") (pin "1") (pinfunction "1_1") (pintype "passive"))
      (node (ref "C24") (pin "1") (pinfunction "1_1") (pintype "passive"))
      (node (ref "C28") (pin "1") (pinfunction "1_1") (pintype "passive"))
      (node (ref "C29") (pin "1") (pinfunction "1_1") (pintype "passive"))
      (node (ref "C30") (pin "+") (pinfunction "+_+") (pintype "passive"))
      (node (ref "C33") (pin "1") (pinfunction "1_1") (pintype "passive"))
      (node (ref "C5") (pin "1") (pinfunction "1_1") (pintype "passive"))
      (node (ref "C7") (pin "1") (pinfunction "1_1") (pintype "passive"))
      (node (ref "IC2") (pin "8") (pinfunction "V+_8") (pintype "power_in"))
      (node (ref "IC3") (pin "11") (pinfunction "V+_11") (pintype "power_in"))
      (node (ref "IC4") (pin "4") (pinfunction "V+_4") (pintype "power_in"))
      (node (ref "IC6") (pin "11") (pinfunction "V+_11") (pintype "power_in"))
      (node (ref "IC7") (pin "4") (pinfunction "V+_4") (pintype "power_in"))
      (node (ref "IC8") (pin "11") (pinfunction "V+_11") (pintype "power_in"))
      (node (ref "IC9") (pin "OUT") (pinfunction "OUT_OUT") (pintype "passive"))
      (node (ref "J5") (pin "2") (pinfunction "2_2") (pintype "passive"))
    )
    (net (code "60") (name "VEE") (class "Default")
      (node (ref "C14") (pin "2") (pinfunction "2_2") (pintype "passive"))
      (node (ref "C16") (pin "2") (pinfunction "2_2") (pintype "passive"))
      (node (ref "C20") (pin "-") (pinfunction "-_-") (pintype "passive"))
      (node (ref "C23") (pin "2") (pinfunction "2_2") (pintype "passive"))
      (node (ref "C26") (pin "2") (pinfunction "2_2") (pintype "passive"))
      (node (ref "C31") (pin "2") (pinfunction "2_2") (pintype "passive"))
      (node (ref "C35") (pin "2") (pinfunction "2_2") (pintype "passive"))
      (node (ref "C9") (pin "2") (pinfunction "2_2") (pintype "passive"))
      (node (ref "IC2") (pin "4") (pinfunction "V-_4") (pintype "power_in"))
      (node (ref "IC3") (pin "6") (pinfunction "V-_6") (pintype "power_in"))
      (node (ref "IC4") (pin "11") (pinfunction "V-_11") (pintype "power_in"))
      (node (ref "IC5") (pin "OUT") (pinfunction "OUT_OUT") (pintype "passive"))
      (node (ref "IC6") (pin "6") (pinfunction "V-_6") (pintype "power_in"))
      (node (ref "IC7") (pin "11") (pinfunction "V-_11") (pintype "power_in"))
      (node (ref "IC8") (pin "6") (pinfunction "V-_6") (pintype "power_in"))
      (node (ref "R12") (pin "1") (pinfunction "1_1") (pintype "passive"))
      (node (ref "R23") (pin "1") (pinfunction "1_1") (pintype "passive"))
      (node (ref "R9") (pin "1") (pinfunction "1_1") (pintype "passive"))
    )
    (net (code "61") (name "unconnected-(IC1-Pad1)") (class "Default")
      (node (ref "IC1") (pin "1") (pinfunction "1_1") (pintype "passive"))
    )
    (net (code "62") (name "unconnected-(IC1-Pad6)") (class "Default")
      (node (ref "IC1") (pin "6") (pinfunction "6_6") (pintype "passive"))
    )
    (net (code "63") (name "unconnected-(IC3A-B-Pad7)") (class "Default")
      (node (ref "IC3") (pin "7") (pinfunction "B_7") (pintype "passive"))
    )
    (net (code "64") (name "unconnected-(IC3A-E-Pad8)") (class "Default")
      (node (ref "IC3") (pin "8") (pinfunction "E_8") (pintype "passive"))
    )
    (net (code "65") (name "unconnected-(IC3B-B-Pad10)") (class "Default")
      (node (ref "IC3") (pin "10") (pinfunction "B_10") (pintype "passive"))
    )
    (net (code "66") (name "unconnected-(IC3B-E-Pad9)") (class "Default")
      (node (ref "IC3") (pin "9") (pinfunction "E_9") (pintype "passive"))
    )
    (net (code "67") (name "unconnected-(IC3C-I_DIODE-Pad2)") (class "Default")
      (node (ref "IC3") (pin "2") (pinfunction "I_DIODE_2") (pintype "input"))
    )
    (net (code "68") (name "unconnected-(IC3D-I_DIODE-Pad15)") (class "Default")
      (node (ref "IC3") (pin "15") (pinfunction "I_DIODE_15") (pintype "input"))
    )
    (net (code "69") (name "unconnected-(IC6A-B-Pad7)") (class "Default")
      (node (ref "IC6") (pin "7") (pinfunction "B_7") (pintype "passive"))
    )
    (net (code "70") (name "unconnected-(IC6A-E-Pad8)") (class "Default")
      (node (ref "IC6") (pin "8") (pinfunction "E_8") (pintype "passive"))
    )
    (net (code "71") (name "unconnected-(IC6B-B-Pad10)") (class "Default")
      (node (ref "IC6") (pin "10") (pinfunction "B_10") (pintype "passive"))
    )
    (net (code "72") (name "unconnected-(IC6B-E-Pad9)") (class "Default")
      (node (ref "IC6") (pin "9") (pinfunction "E_9") (pintype "passive"))
    )
    (net (code "73") (name "unconnected-(IC6C-I_DIODE-Pad2)") (class "Default")
      (node (ref "IC6") (pin "2") (pinfunction "I_DIODE_2") (pintype "input"))
    )
    (net (code "74") (name "unconnected-(IC6D-I_DIODE-Pad15)") (class "Default")
      (node (ref "IC6") (pin "15") (pinfunction "I_DIODE_15") (pintype "input"))
    )
    (net (code "75") (name "unconnected-(IC8A-B-Pad7)") (class "Default")
      (node (ref "IC8") (pin "7") (pinfunction "B_7") (pintype "passive"))
    )
    (net (code "76") (name "unconnected-(IC8A-E-Pad8)") (class "Default")
      (node (ref "IC8") (pin "8") (pinfunction "E_8") (pintype "passive"))
    )
    (net (code "77") (name "unconnected-(IC8B-B-Pad10)") (class "Default")
      (node (ref "IC8") (pin "10") (pinfunction "B_10") (pintype "passive"))
    )
    (net (code "78") (name "unconnected-(IC8B-E-Pad9)") (class "Default")
      (node (ref "IC8") (pin "9") (pinfunction "E_9") (pintype "passive"))
    )
    (net (code "79") (name "unconnected-(IC8C-I_DIODE-Pad2)") (class "Default")
      (node (ref "IC8") (pin "2") (pinfunction "I_DIODE_2") (pintype "input"))
    )
    (net (code "80") (name "unconnected-(IC8D-I_DIODE-Pad15)") (class "Default")
      (node (ref "IC8") (pin "15") (pinfunction "I_DIODE_15") (pintype "input"))
    )
    (net (code "81") (name "unconnected-(J1-Pad2)") (class "Default")
      (node (ref "J1") (pin "2") (pinfunction "2_2") (pintype "passive"))
    )
    (net (code "82") (name "unconnected-(J3-PadTN)") (class "Default")
      (node (ref "J3") (pin "TN") (pinfunction "TN_TN") (pintype "passive"))
    )
    (net (code "83") (name "unconnected-(J4-Pad5)") (class "Default")
      (node (ref "J4") (pin "5") (pinfunction "5_5") (pintype "passive"))
    )
    (net (code "84") (name "unconnected-(J4-Pad6)") (class "Default")
      (node (ref "J4") (pin "6") (pinfunction "6_6") (pintype "passive"))
    )
  )
)
